# dogtag.net
KiCad netlist of a schematic drawn in Altium Designer
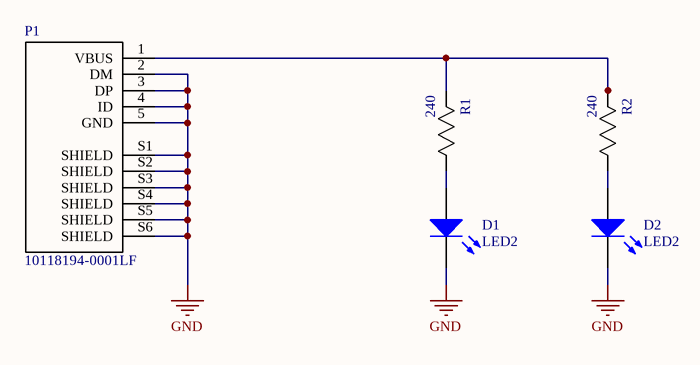
[diagram p0: dogtag.SchDoc]

(export (version "E")
  (design (tool "Eeschema 10.0.6"))
  (components
    (comp (ref "D1")
      (value "LED2")
      (footprint "3.2X1.6X1.1")
      (description "Typical RED, GREEN, YELLOW, AMBER GaAs LED")
      (libsource (lib "AltiumLibraries") (part "LED RED SMD"))
    )
    (comp (ref "D2")
      (value "LED2")
      (footprint "3.2X1.6X1.1")
      (description "Typical RED, GREEN, YELLOW, AMBER GaAs LED")
      (libsource (lib "AltiumLibraries") (part "LED RED SMD"))
    )
    (comp (ref "P1")
      (value "10118194-0001LF")
      (footprint "USB Micro B Receptacle")
      (description "USB - micro B USB 2.0 Receptacle Connector 5 Position Surface Mount, Right Angle; Through Hole")
      (fields (field (name "MF") "Amphenol ICC (FCI)"))
      (libsource (lib "AltiumLibraries") (part "USB Micro B Receptacle"))
    )
    (comp (ref "R1")
      (value "240")
      (footprint "0805")
      (description "RES SMD 240 OHM 5% 1/8W 0805")
      (fields (field (name "TOLERANCE") "5%"))
      (libsource (lib "AltiumLibraries") (part "RES 240.0 1/8W"))
    )
    (comp (ref "R2")
      (value "240")
      (footprint "0805")
      (description "RES SMD 240 OHM 5% 1/8W 0805")
      (fields (field (name "TOLERANCE") "5%"))
      (libsource (lib "") (part "RES 240.0 1/8W_1"))
    )
  )
  (nets
    (net (code "1") (name "GND") (class "Default")
      (node (ref "D1") (pin "2") (pinfunction "K_2") (pintype "passive"))
      (node (ref "D2") (pin "2") (pinfunction "K_2") (pintype "passive"))
      (node (ref "P1") (pin "2") (pinfunction "DM_2") (pintype "passive"))
      (node (ref "P1") (pin "3") (pinfunction "DP_3") (pintype "passive"))
      (node (ref "P1") (pin "4") (pinfunction "ID_4") (pintype "passive"))
      (node (ref "P1") (pin "5") (pinfunction "GND_5") (pintype "passive"))
      (node (ref "P1") (pin "S1") (pinfunction "SHIELD_S1") (pintype "passive"))
      (node (ref "P1") (pin "S2") (pinfunction "SHIELD_S2") (pintype "passive"))
      (node (ref "P1") (pin "S3") (pinfunction "SHIELD_S3") (pintype "passive"))
      (node (ref "P1") (pin "S4") (pinfunction "SHIELD_S4") (pintype "passive"))
      (node (ref "P1") (pin "S5") (pinfunction "SHIELD_S5") (pintype "passive"))
      (node (ref "P1") (pin "S6") (pinfunction "SHIELD_S6") (pintype "passive"))
    )
    (net (code "2") (name "Net-(D1-A)") (class "Default")
      (node (ref "D1") (pin "1") (pinfunction "A_1") (pintype "passive"))
      (node (ref "R1") (pin "1") (pinfunction "R1_1") (pintype "passive"))
    )
    (net (code "3") (name "Net-(D2-A)") (class "Default")
      (node (ref "D2") (pin "1") (pinfunction "A_1") (pintype "passive"))
      (node (ref "R2") (pin "1") (pinfunction "R1_1") (pintype "passive"))
    )
    (net (code "4") (name "Net-(P1-VBUS)") (class "Default")
      (node (ref "P1") (pin "1") (pinfunction "VBUS_1") (pintype "passive"))
      (node (ref "R1") (pin "2") (pinfunction "R2_2") (pintype "passive"))
      (node (ref "R2") (pin "2") (pinfunction "R2_2") (pintype "passive"))
    )
  )
)
